# board.net
KiCad netlist of a schematic drawn in EAGLE
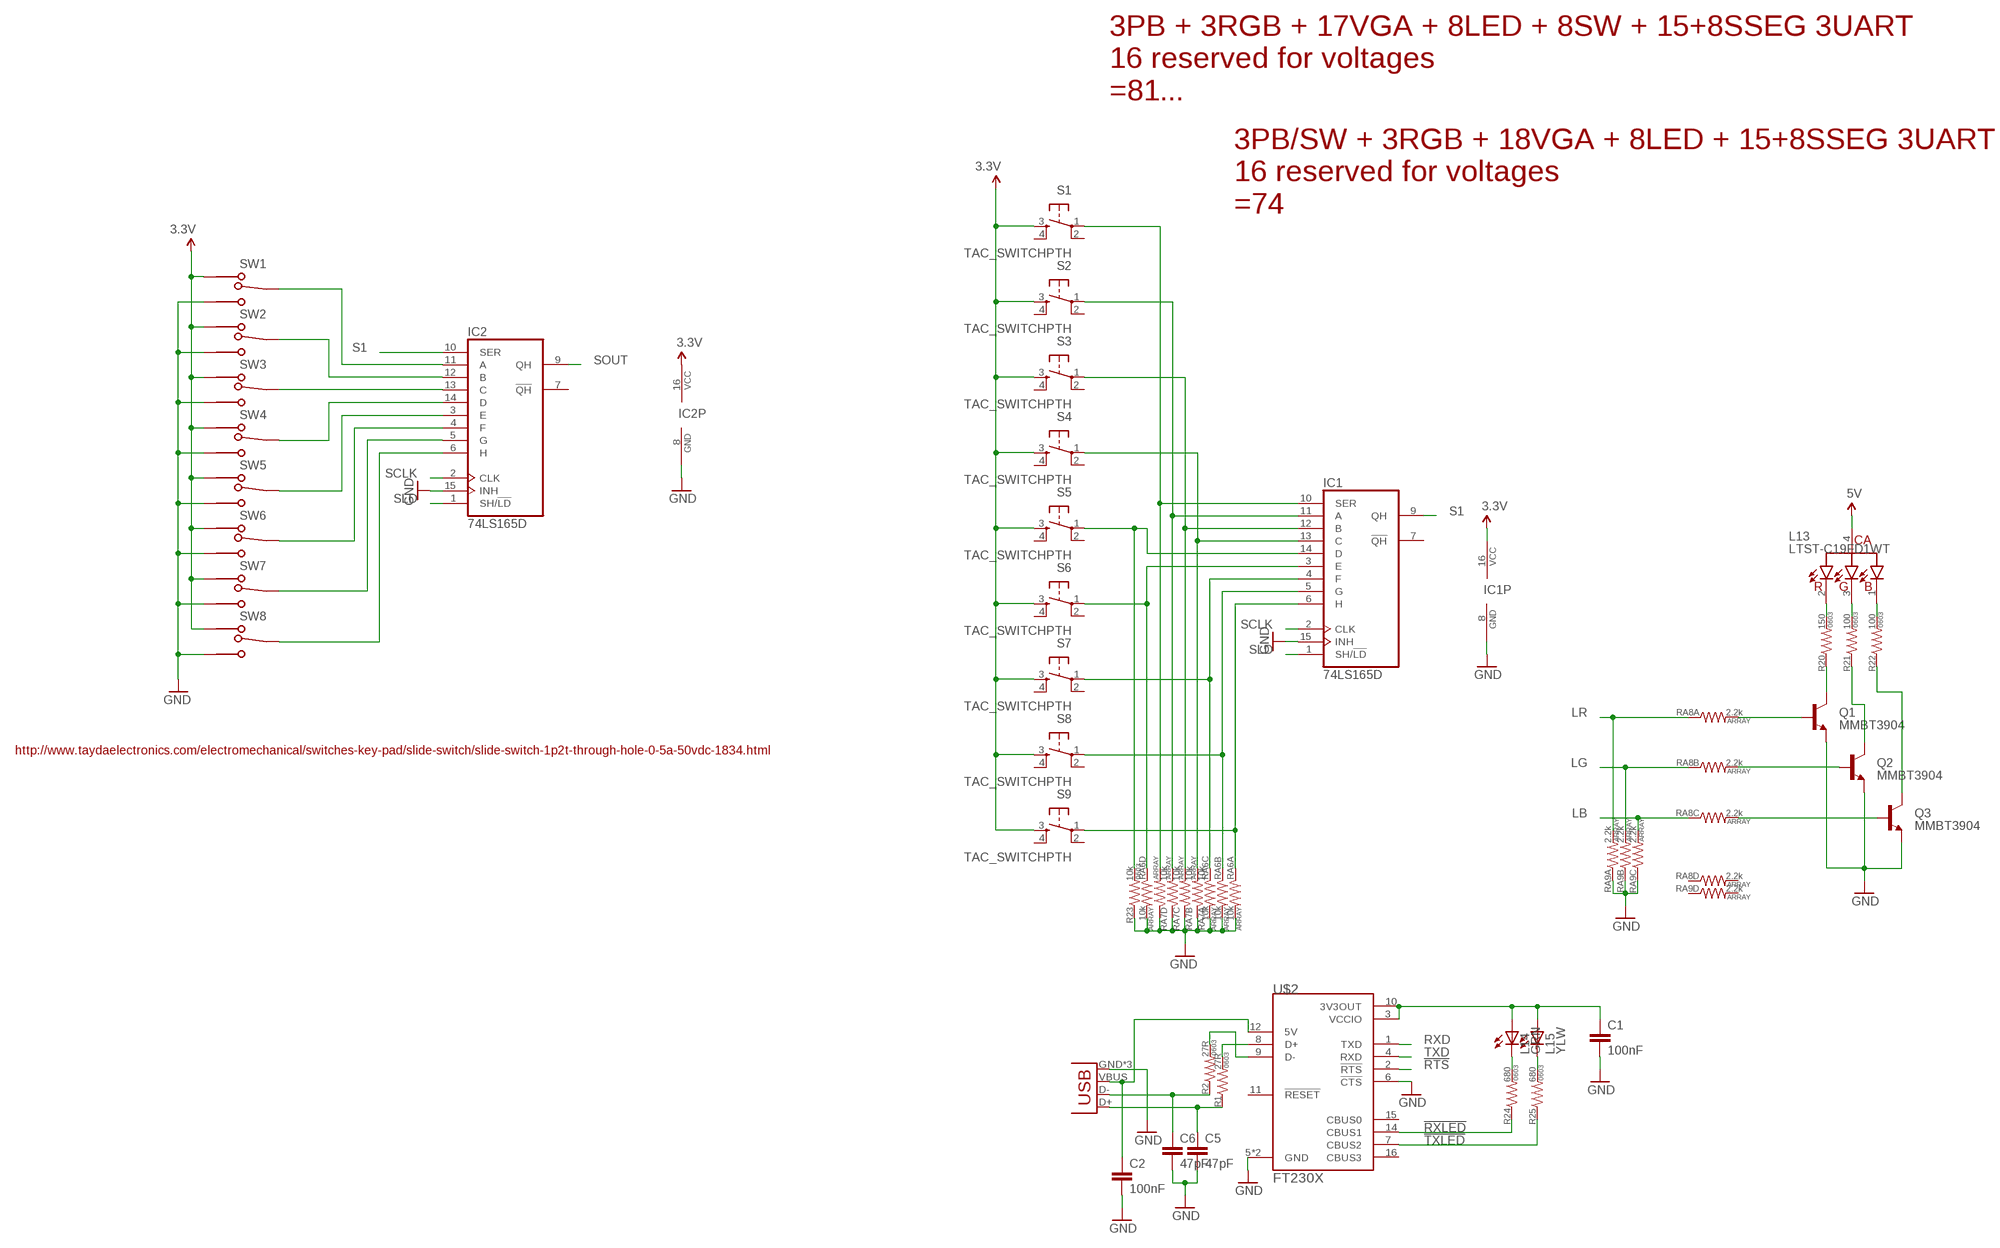
[diagram p0: schematic, sheet 1, part 1 of 3]
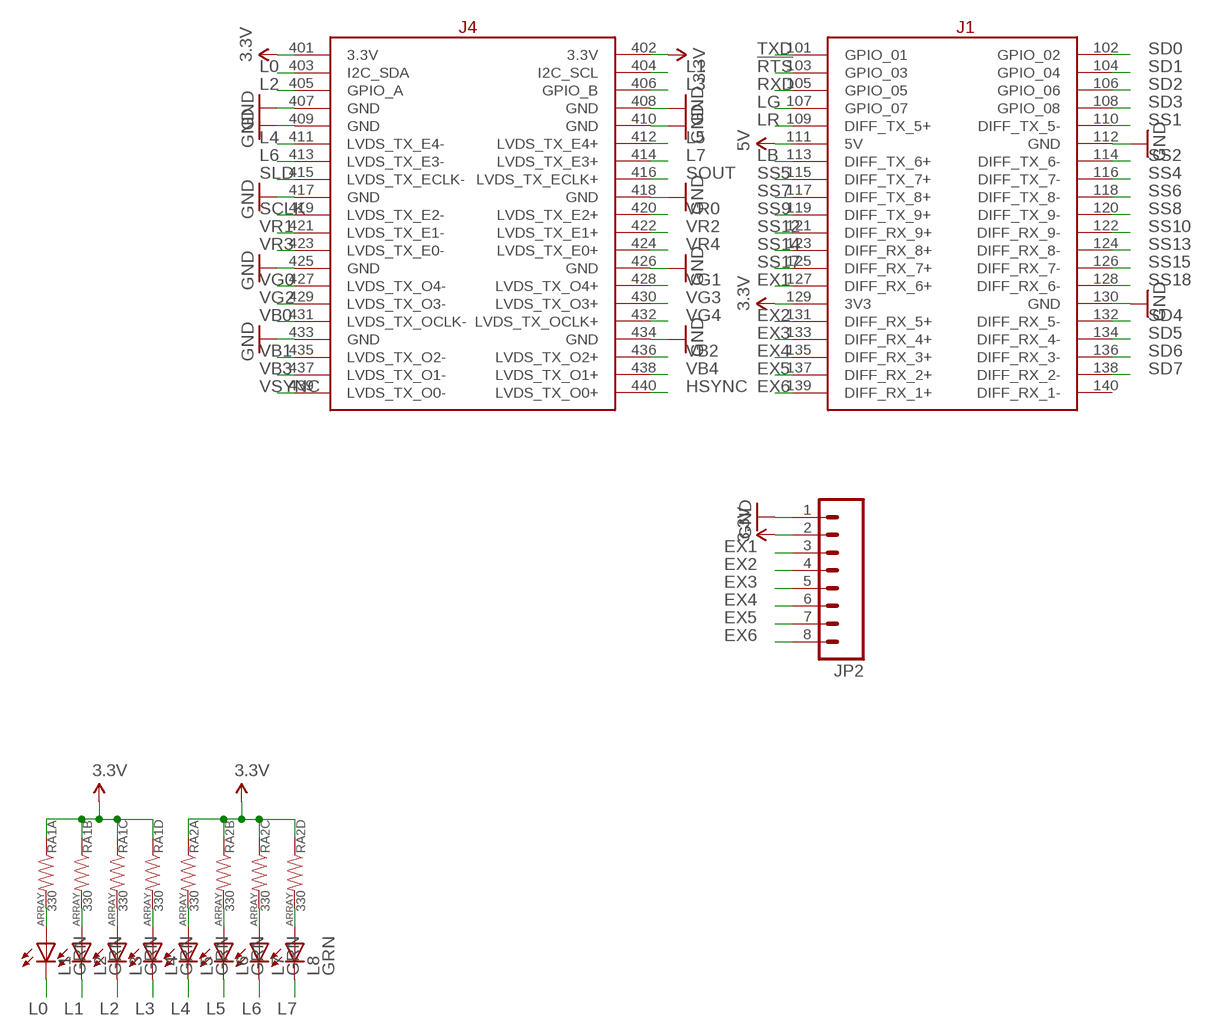
[diagram p1: schematic, sheet 1, part 2 of 3]
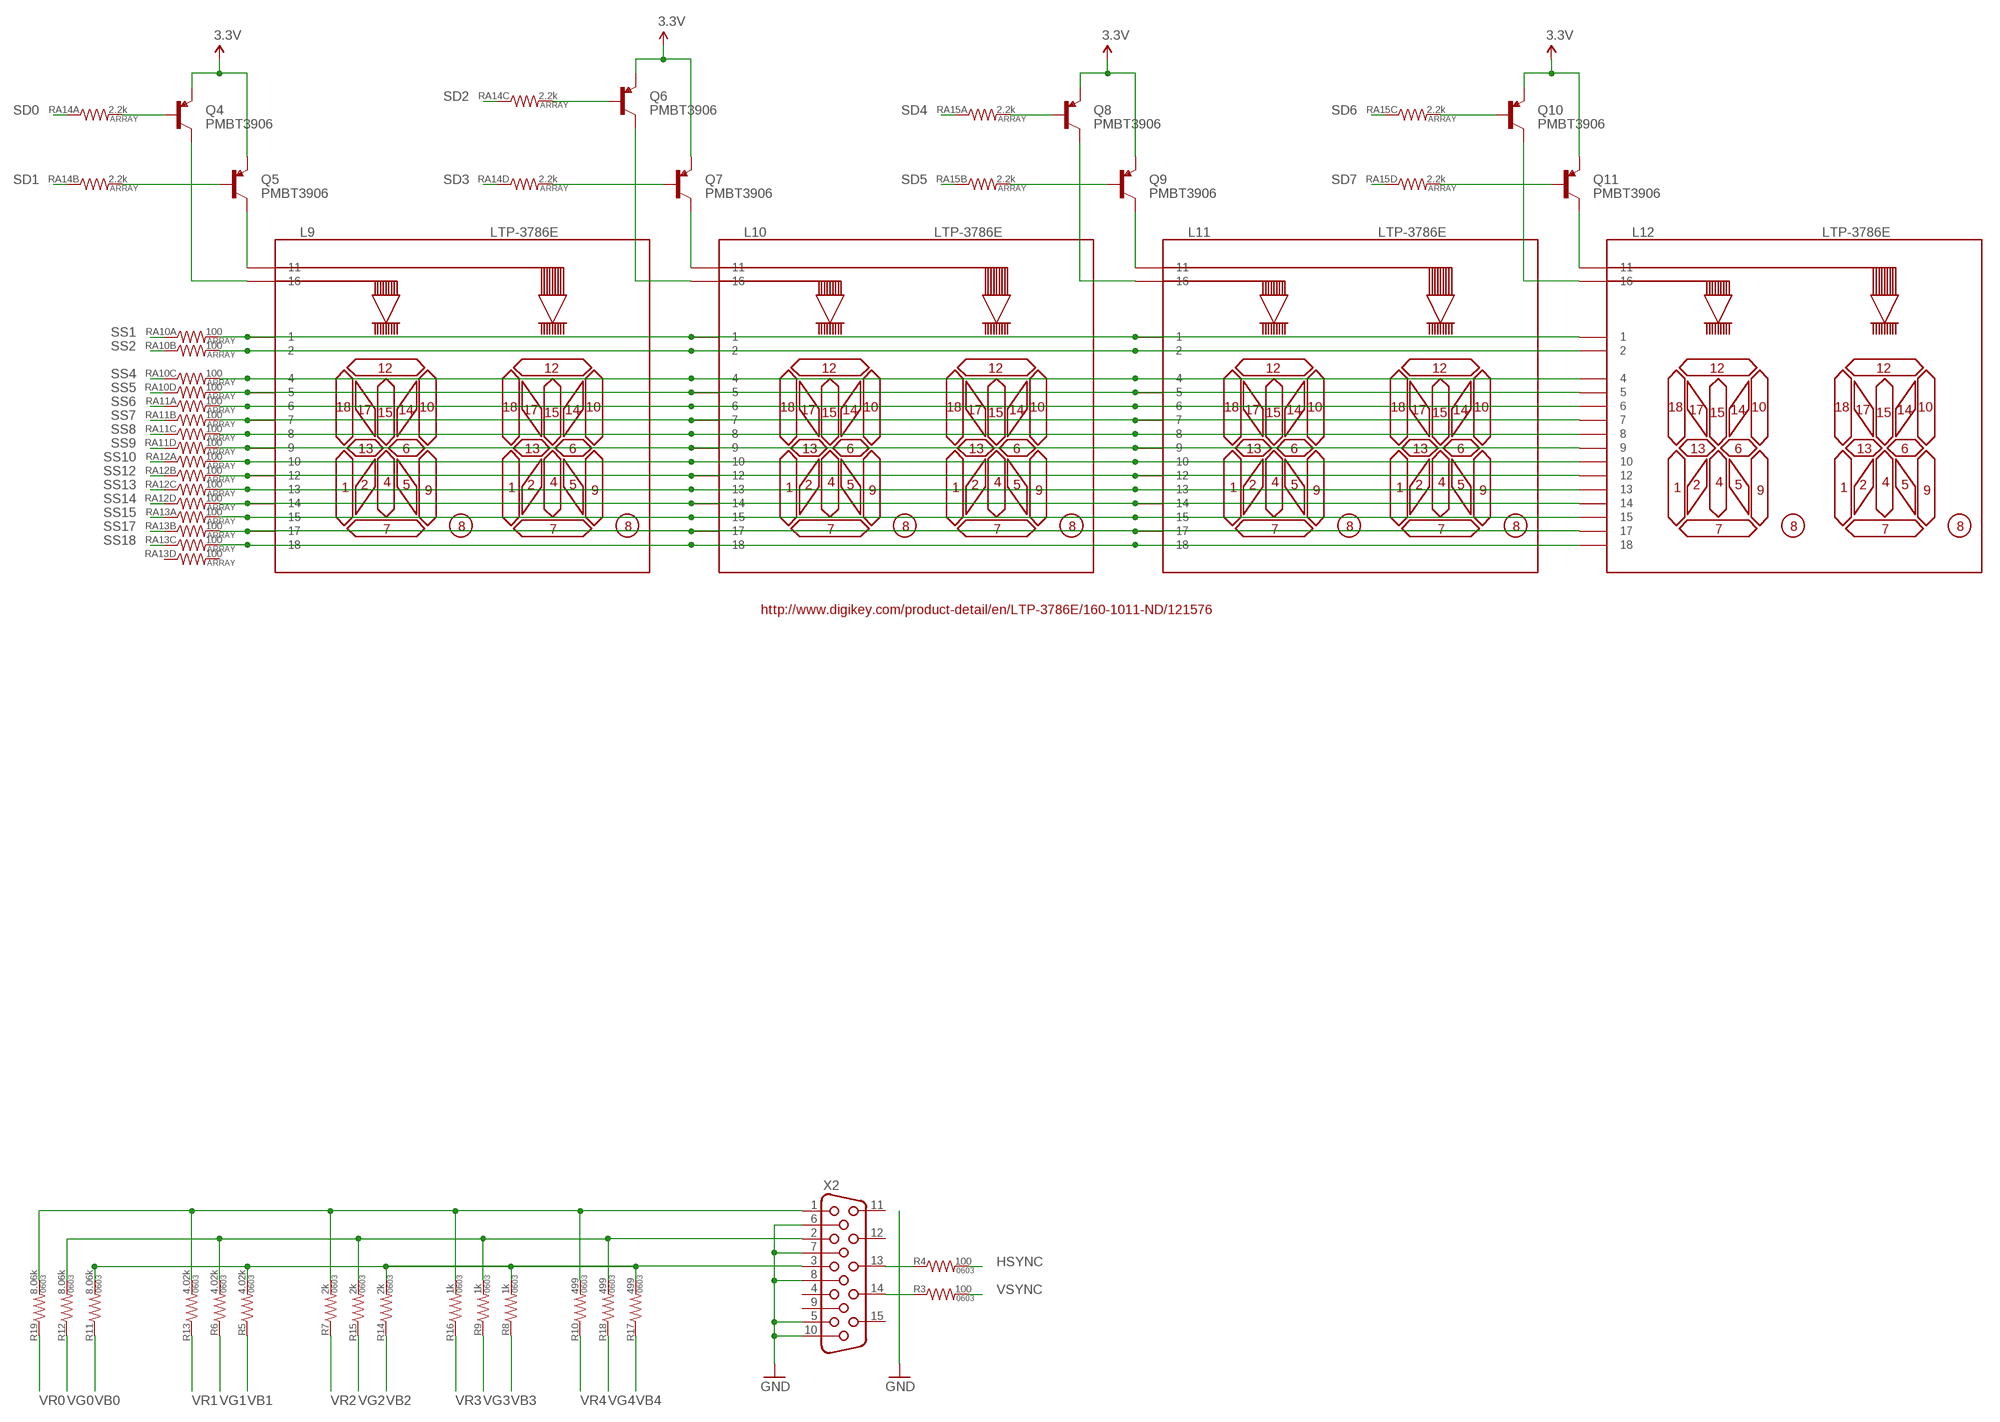
[diagram p2: schematic, sheet 1, part 3 of 3]

(export (version "E")
  (design (tool "Eeschema 10.0.6"))
  (components
    (comp (ref "C1")
      (value "100nF")
      (footprint "eagle-import:0402-CAP")
      (libsource (lib "eagle-import") (part "CAP0402-CAP"))
    )
    (comp (ref "C2")
      (value "100nF")
      (footprint "eagle-import:0402-CAP")
      (libsource (lib "eagle-import") (part "CAP0402-CAP"))
    )
    (comp (ref "C5")
      (value "47pF")
      (footprint "eagle-import:0402-CAP")
      (libsource (lib "eagle-import") (part "CAP0402-CAP"))
    )
    (comp (ref "C6")
      (value "47pF")
      (footprint "eagle-import:0402-CAP")
      (libsource (lib "eagle-import") (part "CAP0402-CAP"))
    )
    (comp (ref "IC1")
      (value "74LS165D")
      (footprint "eagle-import:SO16")
      (libsource (lib "eagle-import") (part "74165DLS"))
    )
    (comp (ref "IC2")
      (value "74LS165D")
      (footprint "eagle-import:SO16")
      (libsource (lib "eagle-import") (part "74165DLS"))
    )
    (comp (ref "JP1")
      (value "USB-MICROB")
      (footprint "eagle-import:USB-MICROB")
      (libsource (lib "eagle-import") (part "USB-MICROB"))
    )
    (comp (ref "JP2")
      (value "M081X08")
      (footprint "eagle-import:1X08")
      (libsource (lib "eagle-import") (part "M081X08"))
    )
    (comp (ref "L1")
      (value "GRN")
      (footprint "eagle-import:0603_LED")
      (libsource (lib "eagle-import") (part "LED0603"))
    )
    (comp (ref "L2")
      (value "GRN")
      (footprint "eagle-import:0603_LED")
      (libsource (lib "eagle-import") (part "LED0603"))
    )
    (comp (ref "L3")
      (value "GRN")
      (footprint "eagle-import:0603_LED")
      (libsource (lib "eagle-import") (part "LED0603"))
    )
    (comp (ref "L4")
      (value "GRN")
      (footprint "eagle-import:0603_LED")
      (libsource (lib "eagle-import") (part "LED0603"))
    )
    (comp (ref "L5")
      (value "GRN")
      (footprint "eagle-import:0603_LED")
      (libsource (lib "eagle-import") (part "LED0603"))
    )
    (comp (ref "L6")
      (value "GRN")
      (footprint "eagle-import:0603_LED")
      (libsource (lib "eagle-import") (part "LED0603"))
    )
    (comp (ref "L7")
      (value "GRN")
      (footprint "eagle-import:0603_LED")
      (libsource (lib "eagle-import") (part "LED0603"))
    )
    (comp (ref "L8")
      (value "GRN")
      (footprint "eagle-import:0603_LED")
      (libsource (lib "eagle-import") (part "LED0603"))
    )
    (comp (ref "L9")
      (value "LTP-3786E")
      (footprint "eagle-import:LTP-378_")
      (libsource (lib "eagle-import") (part "LTP-3786"))
    )
    (comp (ref "L10")
      (value "LTP-3786E")
      (footprint "eagle-import:LTP-378_")
      (libsource (lib "eagle-import") (part "LTP-3786"))
    )
    (comp (ref "L11")
      (value "LTP-3786E")
      (footprint "eagle-import:LTP-378_")
      (libsource (lib "eagle-import") (part "LTP-3786"))
    )
    (comp (ref "L12")
      (value "LTP-3786E")
      (footprint "eagle-import:LTP-378_")
      (libsource (lib "eagle-import") (part "LTP-3786"))
    )
    (comp (ref "L13")
      (value "LTST-C19FD1WT")
      (footprint "eagle-import:LTST-C19F")
      (libsource (lib "eagle-import") (part "LED_RGB"))
    )
    (comp (ref "L14")
      (value "GRN")
      (footprint "eagle-import:0603_LED")
      (libsource (lib "eagle-import") (part "LED0603"))
    )
    (comp (ref "L15")
      (value "YLW")
      (footprint "eagle-import:0603_LED")
      (libsource (lib "eagle-import") (part "LED0603"))
    )
    (comp (ref "Q1")
      (value "MMBT3904")
      (footprint "eagle-import:SOT23")
      (libsource (lib "eagle-import") (part "TRANSISTOR_NPNSOT23"))
    )
    (comp (ref "Q2")
      (value "MMBT3904")
      (footprint "eagle-import:SOT23")
      (libsource (lib "eagle-import") (part "TRANSISTOR_NPNSOT23"))
    )
    (comp (ref "Q3")
      (value "MMBT3904")
      (footprint "eagle-import:SOT23")
      (libsource (lib "eagle-import") (part "TRANSISTOR_NPNSOT23"))
    )
    (comp (ref "Q4")
      (value "PMBT3906")
      (footprint "eagle-import:SOT23-3")
      (libsource (lib "eagle-import") (part "TRANSISTOR_PNPPMBT3906"))
    )
    (comp (ref "Q5")
      (value "PMBT3906")
      (footprint "eagle-import:SOT23-3")
      (libsource (lib "eagle-import") (part "TRANSISTOR_PNPPMBT3906"))
    )
    (comp (ref "Q6")
      (value "PMBT3906")
      (footprint "eagle-import:SOT23-3")
      (libsource (lib "eagle-import") (part "TRANSISTOR_PNPPMBT3906"))
    )
    (comp (ref "Q7")
      (value "PMBT3906")
      (footprint "eagle-import:SOT23-3")
      (libsource (lib "eagle-import") (part "TRANSISTOR_PNPPMBT3906"))
    )
    (comp (ref "Q8")
      (value "PMBT3906")
      (footprint "eagle-import:SOT23-3")
      (libsource (lib "eagle-import") (part "TRANSISTOR_PNPPMBT3906"))
    )
    (comp (ref "Q9")
      (value "PMBT3906")
      (footprint "eagle-import:SOT23-3")
      (libsource (lib "eagle-import") (part "TRANSISTOR_PNPPMBT3906"))
    )
    (comp (ref "Q10")
      (value "PMBT3906")
      (footprint "eagle-import:SOT23-3")
      (libsource (lib "eagle-import") (part "TRANSISTOR_PNPPMBT3906"))
    )
    (comp (ref "Q11")
      (value "PMBT3906")
      (footprint "eagle-import:SOT23-3")
      (libsource (lib "eagle-import") (part "TRANSISTOR_PNPPMBT3906"))
    )
    (comp (ref "R1")
      (value "27R")
      (footprint "eagle-import:0603-RES")
      (libsource (lib "eagle-import") (part "RESISTOR0603"))
    )
    (comp (ref "R2")
      (value "27R")
      (footprint "eagle-import:0603-RES")
      (libsource (lib "eagle-import") (part "RESISTOR0603"))
    )
    (comp (ref "R3")
      (value "100")
      (footprint "eagle-import:0603-RES")
      (libsource (lib "eagle-import") (part "RESISTOR0603"))
    )
    (comp (ref "R4")
      (value "100")
      (footprint "eagle-import:0603-RES")
      (libsource (lib "eagle-import") (part "RESISTOR0603"))
    )
    (comp (ref "R5")
      (value "4.02k")
      (footprint "eagle-import:0603-RES")
      (libsource (lib "eagle-import") (part "RESISTOR0603"))
    )
    (comp (ref "R6")
      (value "4.02k")
      (footprint "eagle-import:0603-RES")
      (libsource (lib "eagle-import") (part "RESISTOR0603"))
    )
    (comp (ref "R7")
      (value "2k")
      (footprint "eagle-import:0603-RES")
      (libsource (lib "eagle-import") (part "RESISTOR0603"))
    )
    (comp (ref "R8")
      (value "1k")
      (footprint "eagle-import:0603-RES")
      (libsource (lib "eagle-import") (part "RESISTOR0603"))
    )
    (comp (ref "R9")
      (value "1k")
      (footprint "eagle-import:0603-RES")
      (libsource (lib "eagle-import") (part "RESISTOR0603"))
    )
    (comp (ref "R10")
      (value "499")
      (footprint "eagle-import:0603-RES")
      (libsource (lib "eagle-import") (part "RESISTOR0603"))
    )
    (comp (ref "R11")
      (value "8.06k")
      (footprint "eagle-import:0603-RES")
      (libsource (lib "eagle-import") (part "RESISTOR0603"))
    )
    (comp (ref "R12")
      (value "8.06k")
      (footprint "eagle-import:0603-RES")
      (libsource (lib "eagle-import") (part "RESISTOR0603"))
    )
    (comp (ref "R13")
      (value "4.02k")
      (footprint "eagle-import:0603-RES")
      (libsource (lib "eagle-import") (part "RESISTOR0603"))
    )
    (comp (ref "R14")
      (value "2k")
      (footprint "eagle-import:0603-RES")
      (libsource (lib "eagle-import") (part "RESISTOR0603"))
    )
    (comp (ref "R15")
      (value "2k")
      (footprint "eagle-import:0603-RES")
      (libsource (lib "eagle-import") (part "RESISTOR0603"))
    )
    (comp (ref "R16")
      (value "1k")
      (footprint "eagle-import:0603-RES")
      (libsource (lib "eagle-import") (part "RESISTOR0603"))
    )
    (comp (ref "R17")
      (value "499")
      (footprint "eagle-import:0603-RES")
      (libsource (lib "eagle-import") (part "RESISTOR0603"))
    )
    (comp (ref "R18")
      (value "499")
      (footprint "eagle-import:0603-RES")
      (libsource (lib "eagle-import") (part "RESISTOR0603"))
    )
    (comp (ref "R19")
      (value "8.06k")
      (footprint "eagle-import:0603-RES")
      (libsource (lib "eagle-import") (part "RESISTOR0603"))
    )
    (comp (ref "R20")
      (value "150")
      (footprint "eagle-import:0603-RES")
      (libsource (lib "eagle-import") (part "RESISTOR0603"))
    )
    (comp (ref "R21")
      (value "100")
      (footprint "eagle-import:0603-RES")
      (libsource (lib "eagle-import") (part "RESISTOR0603"))
    )
    (comp (ref "R22")
      (value "100")
      (footprint "eagle-import:0603-RES")
      (libsource (lib "eagle-import") (part "RESISTOR0603"))
    )
    (comp (ref "R23")
      (value "10k")
      (footprint "eagle-import:0603-RES")
      (libsource (lib "eagle-import") (part "RESISTOR0603"))
    )
    (comp (ref "R24")
      (value "680")
      (footprint "eagle-import:0603-RES")
      (libsource (lib "eagle-import") (part "RESISTOR0603"))
    )
    (comp (ref "R25")
      (value "680")
      (footprint "eagle-import:0603-RES")
      (libsource (lib "eagle-import") (part "RESISTOR0603"))
    )
    (comp (ref "RA1")
      (value "330")
      (footprint "eagle-import:0603-ARV")
      (libsource (lib "eagle-import") (part "RESISTOR_ARRAY0603_X4"))
    )
    (comp (ref "RA2")
      (value "330")
      (footprint "eagle-import:0603-ARV")
      (libsource (lib "eagle-import") (part "RESISTOR_ARRAY0603_X4"))
    )
    (comp (ref "RA6")
      (value "10k")
      (footprint "eagle-import:0603-ARV")
      (libsource (lib "eagle-import") (part "RESISTOR_ARRAY0603_X4"))
    )
    (comp (ref "RA7")
      (value "10k")
      (footprint "eagle-import:0603-ARV")
      (libsource (lib "eagle-import") (part "RESISTOR_ARRAY0603_X4"))
    )
    (comp (ref "RA8")
      (value "2.2k")
      (footprint "eagle-import:0603-ARV")
      (libsource (lib "eagle-import") (part "RESISTOR_ARRAY0603_X4"))
    )
    (comp (ref "RA9")
      (value "2.2k")
      (footprint "eagle-import:0603-ARV")
      (libsource (lib "eagle-import") (part "RESISTOR_ARRAY0603_X4"))
    )
    (comp (ref "RA10")
      (value "100")
      (footprint "eagle-import:0603-ARV")
      (libsource (lib "eagle-import") (part "RESISTOR_ARRAY0603_X4"))
    )
    (comp (ref "RA11")
      (value "100")
      (footprint "eagle-import:0603-ARV")
      (libsource (lib "eagle-import") (part "RESISTOR_ARRAY0603_X4"))
    )
    (comp (ref "RA12")
      (value "100")
      (footprint "eagle-import:0603-ARV")
      (libsource (lib "eagle-import") (part "RESISTOR_ARRAY0603_X4"))
    )
    (comp (ref "RA13")
      (value "100")
      (footprint "eagle-import:0603-ARV")
      (libsource (lib "eagle-import") (part "RESISTOR_ARRAY0603_X4"))
    )
    (comp (ref "RA14")
      (value "2.2k")
      (footprint "eagle-import:0603-ARV")
      (libsource (lib "eagle-import") (part "RESISTOR_ARRAY0603_X4"))
    )
    (comp (ref "RA15")
      (value "2.2k")
      (footprint "eagle-import:0603-ARV")
      (libsource (lib "eagle-import") (part "RESISTOR_ARRAY0603_X4"))
    )
    (comp (ref "S1")
      (value "TAC_SWITCHPTH")
      (footprint "eagle-import:TACTILE-PTH")
      (libsource (lib "eagle-import") (part "TAC_SWITCHPTH"))
    )
    (comp (ref "S2")
      (value "TAC_SWITCHPTH")
      (footprint "eagle-import:TACTILE-PTH")
      (libsource (lib "eagle-import") (part "TAC_SWITCHPTH"))
    )
    (comp (ref "S3")
      (value "TAC_SWITCHPTH")
      (footprint "eagle-import:TACTILE-PTH")
      (libsource (lib "eagle-import") (part "TAC_SWITCHPTH"))
    )
    (comp (ref "S4")
      (value "TAC_SWITCHPTH")
      (footprint "eagle-import:TACTILE-PTH")
      (libsource (lib "eagle-import") (part "TAC_SWITCHPTH"))
    )
    (comp (ref "S5")
      (value "TAC_SWITCHPTH")
      (footprint "eagle-import:TACTILE-PTH")
      (libsource (lib "eagle-import") (part "TAC_SWITCHPTH"))
    )
    (comp (ref "S6")
      (value "TAC_SWITCHPTH")
      (footprint "eagle-import:TACTILE-PTH")
      (libsource (lib "eagle-import") (part "TAC_SWITCHPTH"))
    )
    (comp (ref "S7")
      (value "TAC_SWITCHPTH")
      (footprint "eagle-import:TACTILE-PTH")
      (libsource (lib "eagle-import") (part "TAC_SWITCHPTH"))
    )
    (comp (ref "S8")
      (value "TAC_SWITCHPTH")
      (footprint "eagle-import:TACTILE-PTH")
      (libsource (lib "eagle-import") (part "TAC_SWITCHPTH"))
    )
    (comp (ref "S9")
      (value "TAC_SWITCHPTH")
      (footprint "eagle-import:TACTILE-PTH")
      (libsource (lib "eagle-import") (part "TAC_SWITCHPTH"))
    )
    (comp (ref "SW1")
      (value "SWITCH_SPDT")
      (footprint "eagle-import:SWITCH_SLIDE_SPDT")
      (libsource (lib "eagle-import") (part "SWITCH_SPDT"))
    )
    (comp (ref "SW2")
      (value "SWITCH_SPDT")
      (footprint "eagle-import:SWITCH_SLIDE_SPDT")
      (libsource (lib "eagle-import") (part "SWITCH_SPDT"))
    )
    (comp (ref "SW3")
      (value "SWITCH_SPDT")
      (footprint "eagle-import:SWITCH_SLIDE_SPDT")
      (libsource (lib "eagle-import") (part "SWITCH_SPDT"))
    )
    (comp (ref "SW4")
      (value "SWITCH_SPDT")
      (footprint "eagle-import:SWITCH_SLIDE_SPDT")
      (libsource (lib "eagle-import") (part "SWITCH_SPDT"))
    )
    (comp (ref "SW5")
      (value "SWITCH_SPDT")
      (footprint "eagle-import:SWITCH_SLIDE_SPDT")
      (libsource (lib "eagle-import") (part "SWITCH_SPDT"))
    )
    (comp (ref "SW6")
      (value "SWITCH_SPDT")
      (footprint "eagle-import:SWITCH_SLIDE_SPDT")
      (libsource (lib "eagle-import") (part "SWITCH_SPDT"))
    )
    (comp (ref "SW7")
      (value "SWITCH_SPDT")
      (footprint "eagle-import:SWITCH_SLIDE_SPDT")
      (libsource (lib "eagle-import") (part "SWITCH_SPDT"))
    )
    (comp (ref "SW8")
      (value "SWITCH_SPDT")
      (footprint "eagle-import:SWITCH_SLIDE_SPDT")
      (libsource (lib "eagle-import") (part "SWITCH_SPDT"))
    )
    (comp (ref "U$2")
      (value "FT230X")
      (footprint "eagle-import:TSSOP16")
      (libsource (lib "eagle-import") (part "FT230X"))
    )
    (comp (ref "U$3")
      (value "BEMICROCV_SHIELD")
      (footprint "eagle-import:BEMICROCV_SHIELD")
      (libsource (lib "eagle-import") (part "BEMICROCV_SHIELD"))
    )
    (comp (ref "X2")
      (value "HF15H")
      (footprint "eagle-import:HDF15H")
      (libsource (lib "eagle-import") (part "HF15H"))
    )
  )
  (nets
    (net (code "1") (name "/EX1") (class "Default")
      (node (ref "JP2") (pin "3") (pinfunction "3_3") (pintype "passive"))
      (node (ref "U$3") (pin "127") (pinfunction "DIFF_RX_6+_127") (pintype "bidirectional"))
    )
    (net (code "2") (name "/EX2") (class "Default")
      (node (ref "JP2") (pin "4") (pinfunction "4_4") (pintype "passive"))
      (node (ref "U$3") (pin "131") (pinfunction "DIFF_RX_5+_131") (pintype "bidirectional"))
    )
    (net (code "3") (name "/EX3") (class "Default")
      (node (ref "JP2") (pin "5") (pinfunction "5_5") (pintype "passive"))
      (node (ref "U$3") (pin "133") (pinfunction "DIFF_RX_4+_133") (pintype "bidirectional"))
    )
    (net (code "4") (name "/EX4") (class "Default")
      (node (ref "JP2") (pin "6") (pinfunction "6_6") (pintype "passive"))
      (node (ref "U$3") (pin "135") (pinfunction "DIFF_RX_3+_135") (pintype "bidirectional"))
    )
    (net (code "5") (name "/EX5") (class "Default")
      (node (ref "JP2") (pin "7") (pinfunction "7_7") (pintype "passive"))
      (node (ref "U$3") (pin "137") (pinfunction "DIFF_RX_2+_137") (pintype "bidirectional"))
    )
    (net (code "6") (name "/EX6") (class "Default")
      (node (ref "JP2") (pin "8") (pinfunction "8_8") (pintype "passive"))
      (node (ref "U$3") (pin "139") (pinfunction "DIFF_RX_1+_139") (pintype "bidirectional"))
    )
    (net (code "7") (name "/HSYNC") (class "Default")
      (node (ref "R4") (pin "2") (pinfunction "2_2") (pintype "passive"))
      (node (ref "U$3") (pin "440") (pinfunction "LVDS_TX_O0+_440") (pintype "bidirectional"))
    )
    (net (code "8") (name "/L0") (class "Default")
      (node (ref "L1") (pin "C") (pinfunction "C_C") (pintype "passive"))
      (node (ref "U$3") (pin "403") (pinfunction "I2C_SDA_403") (pintype "bidirectional"))
    )
    (net (code "9") (name "/L1") (class "Default")
      (node (ref "L2") (pin "C") (pinfunction "C_C") (pintype "passive"))
      (node (ref "U$3") (pin "404") (pinfunction "I2C_SCL_404") (pintype "bidirectional"))
    )
    (net (code "10") (name "/L2") (class "Default")
      (node (ref "L3") (pin "C") (pinfunction "C_C") (pintype "passive"))
      (node (ref "U$3") (pin "405") (pinfunction "GPIO_A_405") (pintype "bidirectional"))
    )
    (net (code "11") (name "/L3") (class "Default")
      (node (ref "L4") (pin "C") (pinfunction "C_C") (pintype "passive"))
      (node (ref "U$3") (pin "406") (pinfunction "GPIO_B_406") (pintype "bidirectional"))
    )
    (net (code "12") (name "/L4") (class "Default")
      (node (ref "L5") (pin "C") (pinfunction "C_C") (pintype "passive"))
      (node (ref "U$3") (pin "411") (pinfunction "LVDS_TX_E4-_411") (pintype "bidirectional"))
    )
    (net (code "13") (name "/L5") (class "Default")
      (node (ref "L6") (pin "C") (pinfunction "C_C") (pintype "passive"))
      (node (ref "U$3") (pin "412") (pinfunction "LVDS_TX_E4+_412") (pintype "bidirectional"))
    )
    (net (code "14") (name "/L6") (class "Default")
      (node (ref "L7") (pin "C") (pinfunction "C_C") (pintype "passive"))
      (node (ref "U$3") (pin "413") (pinfunction "LVDS_TX_E3-_413") (pintype "bidirectional"))
    )
    (net (code "15") (name "/L7") (class "Default")
      (node (ref "L8") (pin "C") (pinfunction "C_C") (pintype "passive"))
      (node (ref "U$3") (pin "414") (pinfunction "LVDS_TX_E3+_414") (pintype "bidirectional"))
    )
    (net (code "16") (name "/LB") (class "Default")
      (node (ref "RA8") (pin "3") (pinfunction "1_3") (pintype "passive"))
      (node (ref "RA9") (pin "6") (pinfunction "2_6") (pintype "passive"))
      (node (ref "U$3") (pin "113") (pinfunction "DIFF_TX_6+_113") (pintype "bidirectional"))
    )
    (net (code "17") (name "/LG") (class "Default")
      (node (ref "RA8") (pin "2") (pinfunction "1_2") (pintype "passive"))
      (node (ref "RA9") (pin "7") (pinfunction "2_7") (pintype "passive"))
      (node (ref "U$3") (pin "107") (pinfunction "GPIO_07_107") (pintype "bidirectional"))
    )
    (net (code "18") (name "/LR") (class "Default")
      (node (ref "RA8") (pin "1") (pinfunction "1_1") (pintype "passive"))
      (node (ref "RA9") (pin "8") (pinfunction "2_8") (pintype "passive"))
      (node (ref "U$3") (pin "109") (pinfunction "DIFF_TX_5+_109") (pintype "bidirectional"))
    )
    (net (code "19") (name "/RXD") (class "Default")
      (node (ref "U$2") (pin "1") (pinfunction "TXD_1") (pintype "bidirectional"))
      (node (ref "U$3") (pin "105") (pinfunction "GPIO_05_105") (pintype "bidirectional"))
    )
    (net (code "20") (name "/S1") (class "Default")
      (node (ref "IC1") (pin "9") (pinfunction "QH_9") (pintype "output"))
      (node (ref "IC2") (pin "10") (pinfunction "SER_10") (pintype "input"))
    )
    (net (code "21") (name "/SCLK") (class "Default")
      (node (ref "IC1") (pin "2") (pinfunction "CLK_2") (pintype "input"))
      (node (ref "IC2") (pin "2") (pinfunction "CLK_2") (pintype "input"))
      (node (ref "U$3") (pin "419") (pinfunction "LVDS_TX_E2-_419") (pintype "bidirectional"))
    )
    (net (code "22") (name "/SD0") (class "Default")
      (node (ref "RA14") (pin "1") (pinfunction "1_1") (pintype "passive"))
      (node (ref "U$3") (pin "102") (pinfunction "GPIO_02_102") (pintype "bidirectional"))
    )
    (net (code "23") (name "/SD1") (class "Default")
      (node (ref "RA14") (pin "2") (pinfunction "1_2") (pintype "passive"))
      (node (ref "U$3") (pin "104") (pinfunction "GPIO_04_104") (pintype "bidirectional"))
    )
    (net (code "24") (name "/SD2") (class "Default")
      (node (ref "RA14") (pin "3") (pinfunction "1_3") (pintype "passive"))
      (node (ref "U$3") (pin "106") (pinfunction "GPIO_06_106") (pintype "bidirectional"))
    )
    (net (code "25") (name "/SD3") (class "Default")
      (node (ref "RA14") (pin "4") (pinfunction "1_4") (pintype "passive"))
      (node (ref "U$3") (pin "108") (pinfunction "GPIO_08_108") (pintype "bidirectional"))
    )
    (net (code "26") (name "/SD4") (class "Default")
      (node (ref "RA15") (pin "1") (pinfunction "1_1") (pintype "passive"))
      (node (ref "U$3") (pin "132") (pinfunction "DIFF_RX_5-_132") (pintype "bidirectional"))
    )
    (net (code "27") (name "/SD5") (class "Default")
      (node (ref "RA15") (pin "2") (pinfunction "1_2") (pintype "passive"))
      (node (ref "U$3") (pin "134") (pinfunction "DIFF_RX_4-_134") (pintype "bidirectional"))
    )
    (net (code "28") (name "/SD6") (class "Default")
      (node (ref "RA15") (pin "3") (pinfunction "1_3") (pintype "passive"))
      (node (ref "U$3") (pin "136") (pinfunction "DIFF_RX_3-_136") (pintype "bidirectional"))
    )
    (net (code "29") (name "/SD7") (class "Default")
      (node (ref "RA15") (pin "4") (pinfunction "1_4") (pintype "passive"))
      (node (ref "U$3") (pin "138") (pinfunction "DIFF_RX_2-_138") (pintype "bidirectional"))
    )
    (net (code "30") (name "/SLD") (class "Default")
      (node (ref "IC1") (pin "1") (pinfunction "SH/~{LD}_1") (pintype "input"))
      (node (ref "IC2") (pin "1") (pinfunction "SH/~{LD}_1") (pintype "input"))
      (node (ref "U$3") (pin "415") (pinfunction "LVDS_TX_ECLK-_415") (pintype "bidirectional"))
    )
    (net (code "31") (name "/SOUT") (class "Default")
      (node (ref "IC2") (pin "9") (pinfunction "QH_9") (pintype "output"))
      (node (ref "U$3") (pin "416") (pinfunction "LVDS_TX_ECLK+_416") (pintype "bidirectional"))
    )
    (net (code "32") (name "/SS1") (class "Default")
      (node (ref "RA10") (pin "1") (pinfunction "1_1") (pintype "passive"))
      (node (ref "U$3") (pin "110") (pinfunction "DIFF_TX_5-_110") (pintype "bidirectional"))
    )
    (net (code "33") (name "/SS2") (class "Default")
      (node (ref "RA10") (pin "2") (pinfunction "1_2") (pintype "passive"))
      (node (ref "U$3") (pin "114") (pinfunction "DIFF_TX_6-_114") (pintype "bidirectional"))
    )
    (net (code "34") (name "/SS4") (class "Default")
      (node (ref "RA10") (pin "3") (pinfunction "1_3") (pintype "passive"))
      (node (ref "U$3") (pin "116") (pinfunction "DIFF_TX_7-_116") (pintype "bidirectional"))
    )
    (net (code "35") (name "/SS5") (class "Default")
      (node (ref "RA10") (pin "4") (pinfunction "1_4") (pintype "passive"))
      (node (ref "U$3") (pin "115") (pinfunction "DIFF_TX_7+_115") (pintype "bidirectional"))
    )
    (net (code "36") (name "/SS6") (class "Default")
      (node (ref "RA11") (pin "1") (pinfunction "1_1") (pintype "passive"))
      (node (ref "U$3") (pin "118") (pinfunction "DIFF_TX_8-_118") (pintype "bidirectional"))
    )
    (net (code "37") (name "/SS7") (class "Default")
      (node (ref "RA11") (pin "2") (pinfunction "1_2") (pintype "passive"))
      (node (ref "U$3") (pin "117") (pinfunction "DIFF_TX_8+_117") (pintype "bidirectional"))
    )
    (net (code "38") (name "/SS8") (class "Default")
      (node (ref "RA11") (pin "3") (pinfunction "1_3") (pintype "passive"))
      (node (ref "U$3") (pin "120") (pinfunction "DIFF_TX_9-_120") (pintype "bidirectional"))
    )
    (net (code "39") (name "/SS9") (class "Default")
      (node (ref "RA11") (pin "4") (pinfunction "1_4") (pintype "passive"))
      (node (ref "U$3") (pin "119") (pinfunction "DIFF_TX_9+_119") (pintype "bidirectional"))
    )
    (net (code "40") (name "/SS10") (class "Default")
      (node (ref "RA12") (pin "1") (pinfunction "1_1") (pintype "passive"))
      (node (ref "U$3") (pin "122") (pinfunction "DIFF_RX_9-_122") (pintype "bidirectional"))
    )
    (net (code "41") (name "/SS12") (class "Default")
      (node (ref "RA12") (pin "2") (pinfunction "1_2") (pintype "passive"))
      (node (ref "U$3") (pin "121") (pinfunction "DIFF_RX_9+_121") (pintype "bidirectional"))
    )
    (net (code "42") (name "/SS13") (class "Default")
      (node (ref "RA12") (pin "3") (pinfunction "1_3") (pintype "passive"))
      (node (ref "U$3") (pin "124") (pinfunction "DIFF_RX_8-_124") (pintype "bidirectional"))
    )
    (net (code "43") (name "/SS14") (class "Default")
      (node (ref "RA12") (pin "4") (pinfunction "1_4") (pintype "passive"))
      (node (ref "U$3") (pin "123") (pinfunction "DIFF_RX_8+_123") (pintype "bidirectional"))
    )
    (net (code "44") (name "/SS15") (class "Default")
      (node (ref "RA13") (pin "1") (pinfunction "1_1") (pintype "passive"))
      (node (ref "U$3") (pin "126") (pinfunction "DIFF_RX_7-_126") (pintype "bidirectional"))
    )
    (net (code "45") (name "/SS17") (class "Default")
      (node (ref "RA13") (pin "2") (pinfunction "1_2") (pintype "passive"))
      (node (ref "U$3") (pin "125") (pinfunction "DIFF_RX_7+_125") (pintype "bidirectional"))
    )
    (net (code "46") (name "/SS18") (class "Default")
      (node (ref "RA13") (pin "3") (pinfunction "1_3") (pintype "passive"))
      (node (ref "U$3") (pin "128") (pinfunction "DIFF_RX_6-_128") (pintype "bidirectional"))
    )
    (net (code "47") (name "/TXD") (class "Default")
      (node (ref "U$2") (pin "4") (pinfunction "RXD_4") (pintype "bidirectional"))
      (node (ref "U$3") (pin "101") (pinfunction "GPIO_01_101") (pintype "bidirectional"))
    )
    (net (code "48") (name "/VB0") (class "Default")
      (node (ref "R11") (pin "1") (pinfunction "1_1") (pintype "passive"))
      (node (ref "U$3") (pin "431") (pinfunction "LVDS_TX_OCLK-_431") (pintype "bidirectional"))
    )
    (net (code "49") (name "/VB1") (class "Default")
      (node (ref "R5") (pin "1") (pinfunction "1_1") (pintype "passive"))
      (node (ref "U$3") (pin "435") (pinfunction "LVDS_TX_O2-_435") (pintype "bidirectional"))
    )
    (net (code "50") (name "/VB2") (class "Default")
      (node (ref "R14") (pin "1") (pinfunction "1_1") (pintype "passive"))
      (node (ref "U$3") (pin "436") (pinfunction "LVDS_TX_O2+_436") (pintype "bidirectional"))
    )
    (net (code "51") (name "/VB3") (class "Default")
      (node (ref "R8") (pin "1") (pinfunction "1_1") (pintype "passive"))
      (node (ref "U$3") (pin "437") (pinfunction "LVDS_TX_O1-_437") (pintype "bidirectional"))
    )
    (net (code "52") (name "/VB4") (class "Default")
      (node (ref "R17") (pin "1") (pinfunction "1_1") (pintype "passive"))
      (node (ref "U$3") (pin "438") (pinfunction "LVDS_TX_O1+_438") (pintype "bidirectional"))
    )
    (net (code "53") (name "/VG0") (class "Default")
      (node (ref "R12") (pin "1") (pinfunction "1_1") (pintype "passive"))
      (node (ref "U$3") (pin "427") (pinfunction "LVDS_TX_O4-_427") (pintype "bidirectional"))
    )
    (net (code "54") (name "/VG1") (class "Default")
      (node (ref "R6") (pin "1") (pinfunction "1_1") (pintype "passive"))
      (node (ref "U$3") (pin "428") (pinfunction "LVDS_TX_O4+_428") (pintype "bidirectional"))
    )
    (net (code "55") (name "/VG2") (class "Default")
      (node (ref "R15") (pin "1") (pinfunction "1_1") (pintype "passive"))
      (node (ref "U$3") (pin "429") (pinfunction "LVDS_TX_O3-_429") (pintype "bidirectional"))
    )
    (net (code "56") (name "/VG3") (class "Default")
      (node (ref "R9") (pin "1") (pinfunction "1_1") (pintype "passive"))
      (node (ref "U$3") (pin "430") (pinfunction "LVDS_TX_O3+_430") (pintype "bidirectional"))
    )
    (net (code "57") (name "/VG4") (class "Default")
      (node (ref "R18") (pin "1") (pinfunction "1_1") (pintype "passive"))
      (node (ref "U$3") (pin "432") (pinfunction "LVDS_TX_OCLK+_432") (pintype "bidirectional"))
    )
    (net (code "58") (name "/VR0") (class "Default")
      (node (ref "R19") (pin "1") (pinfunction "1_1") (pintype "passive"))
      (node (ref "U$3") (pin "420") (pinfunction "LVDS_TX_E2+_420") (pintype "bidirectional"))
    )
    (net (code "59") (name "/VR1") (class "Default")
      (node (ref "R13") (pin "1") (pinfunction "1_1") (pintype "passive"))
      (node (ref "U$3") (pin "421") (pinfunction "LVDS_TX_E1-_421") (pintype "bidirectional"))
    )
    (net (code "60") (name "/VR2") (class "Default")
      (node (ref "R7") (pin "1") (pinfunction "1_1") (pintype "passive"))
      (node (ref "U$3") (pin "422") (pinfunction "LVDS_TX_E1+_422") (pintype "bidirectional"))
    )
    (net (code "61") (name "/VR3") (class "Default")
      (node (ref "R16") (pin "1") (pinfunction "1_1") (pintype "passive"))
      (node (ref "U$3") (pin "423") (pinfunction "LVDS_TX_E0-_423") (pintype "bidirectional"))
    )
    (net (code "62") (name "/VR4") (class "Default")
      (node (ref "R10") (pin "1") (pinfunction "1_1") (pintype "passive"))
      (node (ref "U$3") (pin "424") (pinfunction "LVDS_TX_E0+_424") (pintype "bidirectional"))
    )
    (net (code "63") (name "/VSYNC") (class "Default")
      (node (ref "R3") (pin "2") (pinfunction "2_2") (pintype "passive"))
      (node (ref "U$3") (pin "439") (pinfunction "LVDS_TX_O0-_439") (pintype "bidirectional"))
    )
    (net (code "64") (name "/~{RTS}") (class "Default")
      (node (ref "U$2") (pin "2") (pinfunction "~{RTS}_2") (pintype "bidirectional"))
      (node (ref "U$3") (pin "103") (pinfunction "GPIO_03_103") (pintype "bidirectional"))
    )
    (net (code "65") (name "/~{RXLED}") (class "Default")
      (node (ref "R24") (pin "1") (pinfunction "1_1") (pintype "passive"))
      (node (ref "U$2") (pin "14") (pinfunction "CBUS1_14") (pintype "bidirectional"))
    )
    (net (code "66") (name "/~{TXLED}") (class "Default")
      (node (ref "R25") (pin "1") (pinfunction "1_1") (pintype "passive"))
      (node (ref "U$2") (pin "7") (pinfunction "CBUS2_7") (pintype "bidirectional"))
    )
    (net (code "67") (name "3.3V") (class "Default")
      (node (ref "IC1") (pin "16") (pinfunction "VCC_16") (pintype "power_in"))
      (node (ref "IC2") (pin "16") (pinfunction "VCC_16") (pintype "power_in"))
      (node (ref "JP2") (pin "2") (pinfunction "2_2") (pintype "passive"))
      (node (ref "Q10") (pin "2") (pinfunction "E_2") (pintype "passive"))
      (node (ref "Q11") (pin "2") (pinfunction "E_2") (pintype "passive"))
      (node (ref "Q4") (pin "2") (pinfunction "E_2") (pintype "passive"))
      (node (ref "Q5") (pin "2") (pinfunction "E_2") (pintype "passive"))
      (node (ref "Q6") (pin "2") (pinfunction "E_2") (pintype "passive"))
      (node (ref "Q7") (pin "2") (pinfunction "E_2") (pintype "passive"))
      (node (ref "Q8") (pin "2") (pinfunction "E_2") (pintype "passive"))
      (node (ref "Q9") (pin "2") (pinfunction "E_2") (pintype "passive"))
      (node (ref "RA1") (pin "1") (pinfunction "1_1") (pintype "passive"))
      (node (ref "RA1") (pin "2") (pinfunction "1_2") (pintype "passive"))
      (node (ref "RA1") (pin "3") (pinfunction "1_3") (pintype "passive"))
      (node (ref "RA1") (pin "4") (pinfunction "1_4") (pintype "passive"))
      (node (ref "RA2") (pin "1") (pinfunction "1_1") (pintype "passive"))
      (node (ref "RA2") (pin "2") (pinfunction "1_2") (pintype "passive"))
      (node (ref "RA2") (pin "3") (pinfunction "1_3") (pintype "passive"))
      (node (ref "RA2") (pin "4") (pinfunction "1_4") (pintype "passive"))
      (node (ref "S1") (pin "3") (pinfunction "3_3") (pintype "passive"))
      (node (ref "S2") (pin "3") (pinfunction "3_3") (pintype "passive"))
      (node (ref "S3") (pin "3") (pinfunction "3_3") (pintype "passive"))
      (node (ref "S4") (pin "3") (pinfunction "3_3") (pintype "passive"))
      (node (ref "S5") (pin "3") (pinfunction "3_3") (pintype "passive"))
      (node (ref "S6") (pin "3") (pinfunction "3_3") (pintype "passive"))
      (node (ref "S7") (pin "3") (pinfunction "3_3") (pintype "passive"))
      (node (ref "S8") (pin "3") (pinfunction "3_3") (pintype "passive"))
      (node (ref "S9") (pin "3") (pinfunction "3_3") (pintype "passive"))
      (node (ref "SW1") (pin "P1") (pinfunction "P1_P1") (pintype "bidirectional"))
      (node (ref "SW2") (pin "P1") (pinfunction "P1_P1") (pintype "bidirectional"))
      (node (ref "SW3") (pin "P1") (pinfunction "P1_P1") (pintype "bidirectional"))
      (node (ref "SW4") (pin "P1") (pinfunction "P1_P1") (pintype "bidirectional"))
      (node (ref "SW5") (pin "P1") (pinfunction "P1_P1") (pintype "bidirectional"))
      (node (ref "SW6") (pin "P1") (pinfunction "P1_P1") (pintype "bidirectional"))
      (node (ref "SW7") (pin "P1") (pinfunction "P1_P1") (pintype "bidirectional"))
      (node (ref "SW8") (pin "P1") (pinfunction "P1_P1") (pintype "bidirectional"))
      (node (ref "U$3") (pin "129") (pinfunction "3V3_129") (pintype "bidirectional"))
      (node (ref "U$3") (pin "401") (pinfunction "3.3V_401") (pintype "bidirectional"))
      (node (ref "U$3") (pin "402") (pinfunction "3.3V_402") (pintype "bidirectional"))
    )
    (net (code "68") (name "5V") (class "Default")
      (node (ref "L13") (pin "4") (pinfunction "CA_4") (pintype "passive"))
      (node (ref "U$3") (pin "111") (pinfunction "5V_111") (pintype "bidirectional"))
    )
    (net (code "69") (name "GND") (class "Default")
      (node (ref "C1") (pin "2") (pinfunction "2_2") (pintype "passive"))
      (node (ref "C2") (pin "2") (pinfunction "2_2") (pintype "passive"))
      (node (ref "C5") (pin "2") (pinfunction "2_2") (pintype "passive"))
      (node (ref "C6") (pin "2") (pinfunction "2_2") (pintype "passive"))
      (node (ref "IC1") (pin "15") (pinfunction "INH_15") (pintype "input"))
      (node (ref "IC1") (pin "8") (pinfunction "GND_8") (pintype "power_in"))
      (node (ref "IC2") (pin "15") (pinfunction "INH_15") (pintype "input"))
      (node (ref "IC2") (pin "8") (pinfunction "GND_8") (pintype "power_in"))
      (node (ref "JP1") (pin "GND") (pinfunction "GND_GND") (pintype "bidirectional"))
      (node (ref "JP1") (pin "MT1") (pinfunction "GND_MT1") (pintype "bidirectional"))
      (node (ref "JP1") (pin "MT2") (pinfunction "GND_MT2") (pintype "bidirectional"))
      (node (ref "JP2") (pin "1") (pinfunction "1_1") (pintype "passive"))
      (node (ref "Q1") (pin "2") (pinfunction "E_2") (pintype "passive"))
      (node (ref "Q2") (pin "2") (pinfunction "E_2") (pintype "passive"))
      (node (ref "Q3") (pin "2") (pinfunction "E_2") (pintype "passive"))
      (node (ref "R23") (pin "1") (pinfunction "1_1") (pintype "passive"))
      (node (ref "RA6") (pin "5") (pinfunction "2_5") (pintype "passive"))
      (node (ref "RA6") (pin "6") (pinfunction "2_6") (pintype "passive"))
      (node (ref "RA6") (pin "7") (pinfunction "2_7") (pintype "passive"))
      (node (ref "RA6") (pin "8") (pinfunction "2_8") (pintype "passive"))
      (node (ref "RA7") (pin "1") (pinfunction "1_1") (pintype "passive"))
      (node (ref "RA7") (pin "2") (pinfunction "1_2") (pintype "passive"))
      (node (ref "RA7") (pin "3") (pinfunction "1_3") (pintype "passive"))
      (node (ref "RA7") (pin "4") (pinfunction "1_4") (pintype "passive"))
      (node (ref "RA9") (pin "1") (pinfunction "1_1") (pintype "passive"))
      (node (ref "RA9") (pin "2") (pinfunction "1_2") (pintype "passive"))
      (node (ref "RA9") (pin "3") (pinfunction "1_3") (pintype "passive"))
      (node (ref "SW1") (pin "P2") (pinfunction "P2_P2") (pintype "bidirectional"))
      (node (ref "SW2") (pin "P2") (pinfunction "P2_P2") (pintype "bidirectional"))
      (node (ref "SW3") (pin "P2") (pinfunction "P2_P2") (pintype "bidirectional"))
      (node (ref "SW4") (pin "P2") (pinfunction "P2_P2") (pintype "bidirectional"))
      (node (ref "SW5") (pin "P2") (pinfunction "P2_P2") (pintype "bidirectional"))
      (node (ref "SW6") (pin "P2") (pinfunction "P2_P2") (pintype "bidirectional"))
      (node (ref "SW7") (pin "P2") (pinfunction "P2_P2") (pintype "bidirectional"))
      (node (ref "SW8") (pin "P2") (pinfunction "P2_P2") (pintype "bidirectional"))
      (node (ref "U$2") (pin "13") (pinfunction "GND_13") (pintype "bidirectional"))
      (node (ref "U$2") (pin "5") (pinfunction "GND_5") (pintype "bidirectional"))
      (node (ref "U$2") (pin "6") (pinfunction "~{CTS}_6") (pintype "bidirectional"))
      (node (ref "U$3") (pin "112") (pinfunction "GND_112") (pintype "bidirectional"))
      (node (ref "U$3") (pin "130") (pinfunction "GND_130") (pintype "bidirectional"))
      (node (ref "U$3") (pin "407") (pinfunction "GND_407") (pintype "bidirectional"))
      (node (ref "U$3") (pin "408") (pinfunction "GND_408") (pintype "bidirectional"))
      (node (ref "U$3") (pin "409") (pinfunction "GND_409") (pintype "bidirectional"))
      (node (ref "U$3") (pin "410") (pinfunction "GND_410") (pintype "bidirectional"))
      (node (ref "U$3") (pin "417") (pinfunction "GND_417") (pintype "bidirectional"))
      (node (ref "U$3") (pin "418") (pinfunction "GND_418") (pintype "bidirectional"))
      (node (ref "U$3") (pin "425") (pinfunction "GND_425") (pintype "bidirectional"))
      (node (ref "U$3") (pin "426") (pinfunction "GND_426") (pintype "bidirectional"))
      (node (ref "U$3") (pin "433") (pinfunction "GND_433") (pintype "bidirectional"))
      (node (ref "U$3") (pin "434") (pinfunction "GND_434") (pintype "bidirectional"))
      (node (ref "X2") (pin "10") (pinfunction "10_10") (pintype "passive"))
      (node (ref "X2") (pin "5") (pinfunction "5_5") (pintype "passive"))
      (node (ref "X2") (pin "6") (pinfunction "6_6") (pintype "passive"))
      (node (ref "X2") (pin "7") (pinfunction "7_7") (pintype "passive"))
      (node (ref "X2") (pin "8") (pinfunction "8_8") (pintype "passive"))
    )
    (net (code "70") (name "Net-(C5-Pad1)") (class "Default")
      (node (ref "C5") (pin "1") (pinfunction "1_1") (pintype "passive"))
      (node (ref "JP1") (pin "D+") (pinfunction "D+_D+") (pintype "bidirectional"))
      (node (ref "R1") (pin "1") (pinfunction "1_1") (pintype "passive"))
    )
    (net (code "71") (name "Net-(C6-Pad1)") (class "Default")
      (node (ref "C6") (pin "1") (pinfunction "1_1") (pintype "passive"))
      (node (ref "JP1") (pin "D-") (pinfunction "D-_D-") (pintype "bidirectional"))
      (node (ref "R2") (pin "1") (pinfunction "1_1") (pintype "passive"))
    )
    (net (code "72") (name "Net-(IC1A-A)") (class "Default")
      (node (ref "IC1") (pin "11") (pinfunction "A_11") (pintype "input"))
      (node (ref "RA7") (pin "6") (pinfunction "2_6") (pintype "passive"))
      (node (ref "S2") (pin "1") (pinfunction "1_1") (pintype "passive"))
    )
    (net (code "73") (name "Net-(IC1A-B)") (class "Default")
      (node (ref "IC1") (pin "12") (pinfunction "B_12") (pintype "input"))
      (node (ref "RA7") (pin "7") (pinfunction "2_7") (pintype "passive"))
      (node (ref "S3") (pin "1") (pinfunction "1_1") (pintype "passive"))
    )
    (net (code "74") (name "Net-(IC1A-C)") (class "Default")
      (node (ref "IC1") (pin "13") (pinfunction "C_13") (pintype "input"))
      (node (ref "RA7") (pin "8") (pinfunction "2_8") (pintype "passive"))
      (node (ref "S4") (pin "1") (pinfunction "1_1") (pintype "passive"))
    )
    (net (code "75") (name "Net-(IC1A-D)") (class "Default")
      (node (ref "IC1") (pin "14") (pinfunction "D_14") (pintype "input"))
      (node (ref "R23") (pin "2") (pinfunction "2_2") (pintype "passive"))
      (node (ref "S5") (pin "1") (pinfunction "1_1") (pintype "passive"))
    )
    (net (code "76") (name "Net-(IC1A-E)") (class "Default")
      (node (ref "IC1") (pin "3") (pinfunction "E_3") (pintype "input"))
      (node (ref "RA6") (pin "4") (pinfunction "1_4") (pintype "passive"))
      (node (ref "S6") (pin "1") (pinfunction "1_1") (pintype "passive"))
    )
    (net (code "77") (name "Net-(IC1A-F)") (class "Default")
      (node (ref "IC1") (pin "4") (pinfunction "F_4") (pintype "input"))
      (node (ref "RA6") (pin "3") (pinfunction "1_3") (pintype "passive"))
      (node (ref "S7") (pin "1") (pinfunction "1_1") (pintype "passive"))
    )
    (net (code "78") (name "Net-(IC1A-G)") (class "Default")
      (node (ref "IC1") (pin "5") (pinfunction "G_5") (pintype "input"))
      (node (ref "RA6") (pin "2") (pinfunction "1_2") (pintype "passive"))
      (node (ref "S8") (pin "1") (pinfunction "1_1") (pintype "passive"))
    )
    (net (code "79") (name "Net-(IC1A-H)") (class "Default")
      (node (ref "IC1") (pin "6") (pinfunction "H_6") (pintype "input"))
      (node (ref "RA6") (pin "1") (pinfunction "1_1") (pintype "passive"))
      (node (ref "S9") (pin "1") (pinfunction "1_1") (pintype "passive"))
    )
    (net (code "80") (name "Net-(IC1A-SER)") (class "Default")
      (node (ref "IC1") (pin "10") (pinfunction "SER_10") (pintype "input"))
      (node (ref "RA7") (pin "5") (pinfunction "2_5") (pintype "passive"))
      (node (ref "S1") (pin "1") (pinfunction "1_1") (pintype "passive"))
    )
    (net (code "81") (name "Net-(IC2A-A)") (class "Default")
      (node (ref "IC2") (pin "11") (pinfunction "A_11") (pintype "input"))
      (node (ref "SW1") (pin "C") (pinfunction "C_C") (pintype "bidirectional"))
    )
    (net (code "82") (name "Net-(IC2A-B)") (class "Default")
      (node (ref "IC2") (pin "12") (pinfunction "B_12") (pintype "input"))
      (node (ref "SW2") (pin "C") (pinfunction "C_C") (pintype "bidirectional"))
    )
    (net (code "83") (name "Net-(IC2A-C)") (class "Default")
      (node (ref "IC2") (pin "13") (pinfunction "C_13") (pintype "input"))
      (node (ref "SW3") (pin "C") (pinfunction "C_C") (pintype "bidirectional"))
    )
    (net (code "84") (name "Net-(IC2A-D)") (class "Default")
      (node (ref "IC2") (pin "14") (pinfunction "D_14") (pintype "input"))
      (node (ref "SW4") (pin "C") (pinfunction "C_C") (pintype "bidirectional"))
    )
    (net (code "85") (name "Net-(IC2A-E)") (class "Default")
      (node (ref "IC2") (pin "3") (pinfunction "E_3") (pintype "input"))
      (node (ref "SW5") (pin "C") (pinfunction "C_C") (pintype "bidirectional"))
    )
    (net (code "86") (name "Net-(IC2A-F)") (class "Default")
      (node (ref "IC2") (pin "4") (pinfunction "F_4") (pintype "input"))
      (node (ref "SW6") (pin "C") (pinfunction "C_C") (pintype "bidirectional"))
    )
    (net (code "87") (name "Net-(IC2A-G)") (class "Default")
      (node (ref "IC2") (pin "5") (pinfunction "G_5") (pintype "input"))
      (node (ref "SW7") (pin "C") (pinfunction "C_C") (pintype "bidirectional"))
    )
    (net (code "88") (name "Net-(IC2A-H)") (class "Default")
      (node (ref "IC2") (pin "6") (pinfunction "H_6") (pintype "input"))
      (node (ref "SW8") (pin "C") (pinfunction "C_C") (pintype "bidirectional"))
    )
    (net (code "89") (name "Net-(L9-11)") (class "Default")
      (node (ref "L9") (pin "P$11") (pinfunction "11_P$11") (pintype "bidirectional"))
      (node (ref "Q5") (pin "3") (pinfunction "C_3") (pintype "passive"))
    )
    (net (code "90") (name "Net-(L9-16)") (class "Default")
      (node (ref "L9") (pin "P$16") (pinfunction "16_P$16") (pintype "bidirectional"))
      (node (ref "Q4") (pin "3") (pinfunction "C_3") (pintype "passive"))
    )
    (net (code "91") (name "Net-(L10-1)") (class "Default")
      (node (ref "L10") (pin "P$1") (pinfunction "1_P$1") (pintype "bidirectional"))
      (node (ref "L11") (pin "P$1") (pinfunction "1_P$1") (pintype "bidirectional"))
      (node (ref "L12") (pin "P$1") (pinfunction "1_P$1") (pintype "bidirectional"))
      (node (ref "L9") (pin "P$1") (pinfunction "1_P$1") (pintype "bidirectional"))
      (node (ref "RA10") (pin "8") (pinfunction "2_8") (pintype "passive"))
    )
    (net (code "92") (name "Net-(L10-2)") (class "Default")
      (node (ref "L10") (pin "P$2") (pinfunction "2_P$2") (pintype "bidirectional"))
      (node (ref "L11") (pin "P$2") (pinfunction "2_P$2") (pintype "bidirectional"))
      (node (ref "L12") (pin "P$2") (pinfunction "2_P$2") (pintype "bidirectional"))
      (node (ref "L9") (pin "P$2") (pinfunction "2_P$2") (pintype "bidirectional"))
      (node (ref "RA10") (pin "7") (pinfunction "2_7") (pintype "passive"))
    )
    (net (code "93") (name "Net-(L10-4)") (class "Default")
      (node (ref "L10") (pin "P$4") (pinfunction "4_P$4") (pintype "bidirectional"))
      (node (ref "L11") (pin "P$4") (pinfunction "4_P$4") (pintype "bidirectional"))
      (node (ref "L12") (pin "P$4") (pinfunction "4_P$4") (pintype "bidirectional"))
      (node (ref "L9") (pin "P$4") (pinfunction "4_P$4") (pintype "bidirectional"))
      (node (ref "RA10") (pin "6") (pinfunction "2_6") (pintype "passive"))
    )
    (net (code "94") (name "Net-(L10-5)") (class "Default")
      (node (ref "L10") (pin "P$5") (pinfunction "5_P$5") (pintype "bidirectional"))
      (node (ref "L11") (pin "P$5") (pinfunction "5_P$5") (pintype "bidirectional"))
      (node (ref "L12") (pin "P$5") (pinfunction "5_P$5") (pintype "bidirectional"))
      (node (ref "L9") (pin "P$5") (pinfunction "5_P$5") (pintype "bidirectional"))
      (node (ref "RA10") (pin "5") (pinfunction "2_5") (pintype "passive"))
    )
    (net (code "95") (name "Net-(L10-6)") (class "Default")
      (node (ref "L10") (pin "P$6") (pinfunction "6_P$6") (pintype "bidirectional"))
      (node (ref "L11") (pin "P$6") (pinfunction "6_P$6") (pintype "bidirectional"))
      (node (ref "L12") (pin "P$6") (pinfunction "6_P$6") (pintype "bidirectional"))
      (node (ref "L9") (pin "P$6") (pinfunction "6_P$6") (pintype "bidirectional"))
      (node (ref "RA11") (pin "8") (pinfunction "2_8") (pintype "passive"))
    )
    (net (code "96") (name "Net-(L10-7)") (class "Default")
      (node (ref "L10") (pin "P$7") (pinfunction "7_P$7") (pintype "bidirectional"))
      (node (ref "L11") (pin "P$7") (pinfunction "7_P$7") (pintype "bidirectional"))
      (node (ref "L12") (pin "P$7") (pinfunction "7_P$7") (pintype "bidirectional"))
      (node (ref "L9") (pin "P$7") (pinfunction "7_P$7") (pintype "bidirectional"))
      (node (ref "RA11") (pin "7") (pinfunction "2_7") (pintype "passive"))
    )
    (net (code "97") (name "Net-(L10-8)") (class "Default")
      (node (ref "L10") (pin "P$8") (pinfunction "8_P$8") (pintype "bidirectional"))
      (node (ref "L11") (pin "P$8") (pinfunction "8_P$8") (pintype "bidirectional"))
      (node (ref "L12") (pin "P$8") (pinfunction "8_P$8") (pintype "bidirectional"))
      (node (ref "L9") (pin "P$8") (pinfunction "8_P$8") (pintype "bidirectional"))
      (node (ref "RA11") (pin "6") (pinfunction "2_6") (pintype "passive"))
    )
    (net (code "98") (name "Net-(L10-9)") (class "Default")
      (node (ref "L10") (pin "P$9") (pinfunction "9_P$9") (pintype "bidirectional"))
      (node (ref "L11") (pin "P$9") (pinfunction "9_P$9") (pintype "bidirectional"))
      (node (ref "L12") (pin "P$9") (pinfunction "9_P$9") (pintype "bidirectional"))
      (node (ref "L9") (pin "P$9") (pinfunction "9_P$9") (pintype "bidirectional"))
      (node (ref "RA11") (pin "5") (pinfunction "2_5") (pintype "passive"))
    )
    (net (code "99") (name "Net-(L10-10)") (class "Default")
      (node (ref "L10") (pin "P$10") (pinfunction "10_P$10") (pintype "bidirectional"))
      (node (ref "L11") (pin "P$10") (pinfunction "10_P$10") (pintype "bidirectional"))
      (node (ref "L12") (pin "P$10") (pinfunction "10_P$10") (pintype "bidirectional"))
      (node (ref "L9") (pin "P$10") (pinfunction "10_P$10") (pintype "bidirectional"))
      (node (ref "RA12") (pin "8") (pinfunction "2_8") (pintype "passive"))
    )
    (net (code "100") (name "Net-(L10-11)") (class "Default")
      (node (ref "L10") (pin "P$11") (pinfunction "11_P$11") (pintype "bidirectional"))
      (node (ref "Q7") (pin "3") (pinfunction "C_3") (pintype "passive"))
    )
    (net (code "101") (name "Net-(L10-12)") (class "Default")
      (node (ref "L10") (pin "P$12") (pinfunction "12_P$12") (pintype "bidirectional"))
      (node (ref "L11") (pin "P$12") (pinfunction "12_P$12") (pintype "bidirectional"))
      (node (ref "L12") (pin "P$12") (pinfunction "12_P$12") (pintype "bidirectional"))
      (node (ref "L9") (pin "P$12") (pinfunction "12_P$12") (pintype "bidirectional"))
      (node (ref "RA12") (pin "7") (pinfunction "2_7") (pintype "passive"))
    )
    (net (code "102") (name "Net-(L10-13)") (class "Default")
      (node (ref "L10") (pin "P$13") (pinfunction "13_P$13") (pintype "bidirectional"))
      (node (ref "L11") (pin "P$13") (pinfunction "13_P$13") (pintype "bidirectional"))
      (node (ref "L12") (pin "P$13") (pinfunction "13_P$13") (pintype "bidirectional"))
      (node (ref "L9") (pin "P$13") (pinfunction "13_P$13") (pintype "bidirectional"))
      (node (ref "RA12") (pin "6") (pinfunction "2_6") (pintype "passive"))
    )
    (net (code "103") (name "Net-(L10-14)") (class "Default")
      (node (ref "L10") (pin "P$14") (pinfunction "14_P$14") (pintype "bidirectional"))
      (node (ref "L11") (pin "P$14") (pinfunction "14_P$14") (pintype "bidirectional"))
      (node (ref "L12") (pin "P$14") (pinfunction "14_P$14") (pintype "bidirectional"))
      (node (ref "L9") (pin "P$14") (pinfunction "14_P$14") (pintype "bidirectional"))
      (node (ref "RA12") (pin "5") (pinfunction "2_5") (pintype "passive"))
    )
    (net (code "104") (name "Net-(L10-15)") (class "Default")
      (node (ref "L10") (pin "P$15") (pinfunction "15_P$15") (pintype "bidirectional"))
      (node (ref "L11") (pin "P$15") (pinfunction "15_P$15") (pintype "bidirectional"))
      (node (ref "L12") (pin "P$15") (pinfunction "15_P$15") (pintype "bidirectional"))
      (node (ref "L9") (pin "P$15") (pinfunction "15_P$15") (pintype "bidirectional"))
      (node (ref "RA13") (pin "8") (pinfunction "2_8") (pintype "passive"))
    )
    (net (code "105") (name "Net-(L10-16)") (class "Default")
      (node (ref "L10") (pin "P$16") (pinfunction "16_P$16") (pintype "bidirectional"))
      (node (ref "Q6") (pin "3") (pinfunction "C_3") (pintype "passive"))
    )
    (net (code "106") (name "Net-(L10-17)") (class "Default")
      (node (ref "L10") (pin "P$17") (pinfunction "17_P$17") (pintype "bidirectional"))
      (node (ref "L11") (pin "P$17") (pinfunction "17_P$17") (pintype "bidirectional"))
      (node (ref "L12") (pin "P$17") (pinfunction "17_P$17") (pintype "bidirectional"))
      (node (ref "L9") (pin "P$17") (pinfunction "17_P$17") (pintype "bidirectional"))
      (node (ref "RA13") (pin "7") (pinfunction "2_7") (pintype "passive"))
    )
    (net (code "107") (name "Net-(L10-18)") (class "Default")
      (node (ref "L10") (pin "P$18") (pinfunction "18_P$18") (pintype "bidirectional"))
      (node (ref "L11") (pin "P$18") (pinfunction "18_P$18") (pintype "bidirectional"))
      (node (ref "L12") (pin "P$18") (pinfunction "18_P$18") (pintype "bidirectional"))
      (node (ref "L9") (pin "P$18") (pinfunction "18_P$18") (pintype "bidirectional"))
      (node (ref "RA13") (pin "6") (pinfunction "2_6") (pintype "passive"))
    )
    (net (code "108") (name "Net-(L11-11)") (class "Default")
      (node (ref "L11") (pin "P$11") (pinfunction "11_P$11") (pintype "bidirectional"))
      (node (ref "Q9") (pin "3") (pinfunction "C_3") (pintype "passive"))
    )
    (net (code "109") (name "Net-(L11-16)") (class "Default")
      (node (ref "L11") (pin "P$16") (pinfunction "16_P$16") (pintype "bidirectional"))
      (node (ref "Q8") (pin "3") (pinfunction "C_3") (pintype "passive"))
    )
    (net (code "110") (name "Net-(L12-11)") (class "Default")
      (node (ref "L12") (pin "P$11") (pinfunction "11_P$11") (pintype "bidirectional"))
      (node (ref "Q11") (pin "3") (pinfunction "C_3") (pintype "passive"))
    )
    (net (code "111") (name "Net-(L12-16)") (class "Default")
      (node (ref "L12") (pin "P$16") (pinfunction "16_P$16") (pintype "bidirectional"))
      (node (ref "Q10") (pin "3") (pinfunction "C_3") (pintype "passive"))
    )
    (net (code "112") (name "Net-(L13-B)") (class "Default")
      (node (ref "L13") (pin "1") (pinfunction "B_1") (pintype "passive"))
      (node (ref "R22") (pin "2") (pinfunction "2_2") (pintype "passive"))
    )
    (net (code "113") (name "Net-(L13-G)") (class "Default")
      (node (ref "L13") (pin "3") (pinfunction "G_3") (pintype "passive"))
      (node (ref "R21") (pin "2") (pinfunction "2_2") (pintype "passive"))
    )
    (net (code "114") (name "Net-(L13-R)") (class "Default")
      (node (ref "L13") (pin "2") (pinfunction "R_2") (pintype "passive"))
      (node (ref "R20") (pin "2") (pinfunction "2_2") (pintype "passive"))
    )
    (net (code "115") (name "Net-(L14-PadC)") (class "Default")
      (node (ref "L14") (pin "C") (pinfunction "C_C") (pintype "passive"))
      (node (ref "R24") (pin "2") (pinfunction "2_2") (pintype "passive"))
    )
    (net (code "116") (name "Net-(L15-PadC)") (class "Default")
      (node (ref "L15") (pin "C") (pinfunction "C_C") (pintype "passive"))
      (node (ref "R25") (pin "2") (pinfunction "2_2") (pintype "passive"))
    )
    (net (code "117") (name "Net-(Q1-B)") (class "Default")
      (node (ref "Q1") (pin "1") (pinfunction "B_1") (pintype "passive"))
      (node (ref "RA8") (pin "8") (pinfunction "2_8") (pintype "passive"))
    )
    (net (code "118") (name "Net-(Q1-C)") (class "Default")
      (node (ref "Q1") (pin "3") (pinfunction "C_3") (pintype "passive"))
      (node (ref "R20") (pin "1") (pinfunction "1_1") (pintype "passive"))
    )
    (net (code "119") (name "Net-(Q2-B)") (class "Default")
      (node (ref "Q2") (pin "1") (pinfunction "B_1") (pintype "passive"))
      (node (ref "RA8") (pin "7") (pinfunction "2_7") (pintype "passive"))
    )
    (net (code "120") (name "Net-(Q2-C)") (class "Default")
      (node (ref "Q2") (pin "3") (pinfunction "C_3") (pintype "passive"))
      (node (ref "R21") (pin "1") (pinfunction "1_1") (pintype "passive"))
    )
    (net (code "121") (name "Net-(Q3-B)") (class "Default")
      (node (ref "Q3") (pin "1") (pinfunction "B_1") (pintype "passive"))
      (node (ref "RA8") (pin "6") (pinfunction "2_6") (pintype "passive"))
    )
    (net (code "122") (name "Net-(Q3-C)") (class "Default")
      (node (ref "Q3") (pin "3") (pinfunction "C_3") (pintype "passive"))
      (node (ref "R22") (pin "1") (pinfunction "1_1") (pintype "passive"))
    )
    (net (code "123") (name "Net-(Q4-B)") (class "Default")
      (node (ref "Q4") (pin "1") (pinfunction "B_1") (pintype "passive"))
      (node (ref "RA14") (pin "8") (pinfunction "2_8") (pintype "passive"))
    )
    (net (code "124") (name "Net-(Q5-B)") (class "Default")
      (node (ref "Q5") (pin "1") (pinfunction "B_1") (pintype "passive"))
      (node (ref "RA14") (pin "7") (pinfunction "2_7") (pintype "passive"))
    )
    (net (code "125") (name "Net-(Q6-B)") (class "Default")
      (node (ref "Q6") (pin "1") (pinfunction "B_1") (pintype "passive"))
      (node (ref "RA14") (pin "6") (pinfunction "2_6") (pintype "passive"))
    )
    (net (code "126") (name "Net-(Q7-B)") (class "Default")
      (node (ref "Q7") (pin "1") (pinfunction "B_1") (pintype "passive"))
      (node (ref "RA14") (pin "5") (pinfunction "2_5") (pintype "passive"))
    )
    (net (code "127") (name "Net-(Q8-B)") (class "Default")
      (node (ref "Q8") (pin "1") (pinfunction "B_1") (pintype "passive"))
      (node (ref "RA15") (pin "8") (pinfunction "2_8") (pintype "passive"))
    )
    (net (code "128") (name "Net-(Q9-B)") (class "Default")
      (node (ref "Q9") (pin "1") (pinfunction "B_1") (pintype "passive"))
      (node (ref "RA15") (pin "7") (pinfunction "2_7") (pintype "passive"))
    )
    (net (code "129") (name "Net-(Q10-B)") (class "Default")
      (node (ref "Q10") (pin "1") (pinfunction "B_1") (pintype "passive"))
      (node (ref "RA15") (pin "6") (pinfunction "2_6") (pintype "passive"))
    )
    (net (code "130") (name "Net-(Q11-B)") (class "Default")
      (node (ref "Q11") (pin "1") (pinfunction "B_1") (pintype "passive"))
      (node (ref "RA15") (pin "5") (pinfunction "2_5") (pintype "passive"))
    )
    (net (code "131") (name "Net-(R3-Pad1)") (class "Default")
      (node (ref "R3") (pin "1") (pinfunction "1_1") (pintype "passive"))
      (node (ref "X2") (pin "14") (pinfunction "14_14") (pintype "passive"))
    )
    (net (code "132") (name "Net-(R4-Pad1)") (class "Default")
      (node (ref "R4") (pin "1") (pinfunction "1_1") (pintype "passive"))
      (node (ref "X2") (pin "13") (pinfunction "13_13") (pintype "passive"))
    )
    (net (code "133") (name "Net-(R10-Pad2)") (class "Default")
      (node (ref "R10") (pin "2") (pinfunction "2_2") (pintype "passive"))
      (node (ref "R13") (pin "2") (pinfunction "2_2") (pintype "passive"))
      (node (ref "R16") (pin "2") (pinfunction "2_2") (pintype "passive"))
      (node (ref "R19") (pin "2") (pinfunction "2_2") (pintype "passive"))
      (node (ref "R7") (pin "2") (pinfunction "2_2") (pintype "passive"))
      (node (ref "X2") (pin "1") (pinfunction "1_1") (pintype "passive"))
    )
    (net (code "134") (name "Net-(R11-Pad2)") (class "Default")
      (node (ref "R11") (pin "2") (pinfunction "2_2") (pintype "passive"))
      (node (ref "R14") (pin "2") (pinfunction "2_2") (pintype "passive"))
      (node (ref "R17") (pin "2") (pinfunction "2_2") (pintype "passive"))
      (node (ref "R5") (pin "2") (pinfunction "2_2") (pintype "passive"))
      (node (ref "R8") (pin "2") (pinfunction "2_2") (pintype "passive"))
      (node (ref "X2") (pin "3") (pinfunction "3_3") (pintype "passive"))
    )
    (net (code "135") (name "Net-(R12-Pad2)") (class "Default")
      (node (ref "R12") (pin "2") (pinfunction "2_2") (pintype "passive"))
      (node (ref "R15") (pin "2") (pinfunction "2_2") (pintype "passive"))
      (node (ref "R18") (pin "2") (pinfunction "2_2") (pintype "passive"))
      (node (ref "R6") (pin "2") (pinfunction "2_2") (pintype "passive"))
      (node (ref "R9") (pin "2") (pinfunction "2_2") (pintype "passive"))
      (node (ref "X2") (pin "2") (pinfunction "2_2") (pintype "passive"))
    )
    (net (code "136") (name "Net-(RA1A-2)") (class "Default")
      (node (ref "L1") (pin "A") (pinfunction "A_A") (pintype "passive"))
      (node (ref "RA1") (pin "8") (pinfunction "2_8") (pintype "passive"))
    )
    (net (code "137") (name "Net-(RA1B-2)") (class "Default")
      (node (ref "L2") (pin "A") (pinfunction "A_A") (pintype "passive"))
      (node (ref "RA1") (pin "7") (pinfunction "2_7") (pintype "passive"))
    )
    (net (code "138") (name "Net-(RA1C-2)") (class "Default")
      (node (ref "L3") (pin "A") (pinfunction "A_A") (pintype "passive"))
      (node (ref "RA1") (pin "6") (pinfunction "2_6") (pintype "passive"))
    )
    (net (code "139") (name "Net-(RA1D-2)") (class "Default")
      (node (ref "L4") (pin "A") (pinfunction "A_A") (pintype "passive"))
      (node (ref "RA1") (pin "5") (pinfunction "2_5") (pintype "passive"))
    )
    (net (code "140") (name "Net-(RA2A-2)") (class "Default")
      (node (ref "L5") (pin "A") (pinfunction "A_A") (pintype "passive"))
      (node (ref "RA2") (pin "8") (pinfunction "2_8") (pintype "passive"))
    )
    (net (code "141") (name "Net-(RA2B-2)") (class "Default")
      (node (ref "L6") (pin "A") (pinfunction "A_A") (pintype "passive"))
      (node (ref "RA2") (pin "7") (pinfunction "2_7") (pintype "passive"))
    )
    (net (code "142") (name "Net-(RA2C-2)") (class "Default")
      (node (ref "L7") (pin "A") (pinfunction "A_A") (pintype "passive"))
      (node (ref "RA2") (pin "6") (pinfunction "2_6") (pintype "passive"))
    )
    (net (code "143") (name "Net-(RA2D-2)") (class "Default")
      (node (ref "L8") (pin "A") (pinfunction "A_A") (pintype "passive"))
      (node (ref "RA2") (pin "5") (pinfunction "2_5") (pintype "passive"))
    )
    (net (code "144") (name "Net-(U$2-3V3OUT)") (class "Default")
      (node (ref "C1") (pin "1") (pinfunction "1_1") (pintype "passive"))
      (node (ref "L14") (pin "A") (pinfunction "A_A") (pintype "passive"))
      (node (ref "L15") (pin "A") (pinfunction "A_A") (pintype "passive"))
      (node (ref "U$2") (pin "10") (pinfunction "3V3OUT_10") (pintype "bidirectional"))
      (node (ref "U$2") (pin "3") (pinfunction "VCCIO_3") (pintype "bidirectional"))
    )
    (net (code "145") (name "Net-(U$2-5V)") (class "Default")
      (node (ref "C2") (pin "1") (pinfunction "1_1") (pintype "passive"))
      (node (ref "JP1") (pin "VBUS") (pinfunction "VBUS_VBUS") (pintype "bidirectional"))
      (node (ref "U$2") (pin "12") (pinfunction "5V_12") (pintype "bidirectional"))
    )
    (net (code "146") (name "Net-(U$2-D+)") (class "Default")
      (node (ref "R1") (pin "2") (pinfunction "2_2") (pintype "passive"))
      (node (ref "U$2") (pin "8") (pinfunction "D+_8") (pintype "bidirectional"))
    )
    (net (code "147") (name "Net-(U$2-D-)") (class "Default")
      (node (ref "R2") (pin "2") (pinfunction "2_2") (pintype "passive"))
      (node (ref "U$2") (pin "9") (pinfunction "D-_9") (pintype "bidirectional"))
    )
    (net (code "148") (name "unconnected-(IC1A-~{QH}-Pad7)") (class "Default")
      (node (ref "IC1") (pin "7") (pinfunction "~{QH}_7") (pintype "output"))
    )
    (net (code "149") (name "unconnected-(IC2A-~{QH}-Pad7)") (class "Default")
      (node (ref "IC2") (pin "7") (pinfunction "~{QH}_7") (pintype "output"))
    )
    (net (code "150") (name "unconnected-(RA8D-1-Pad4)") (class "Default")
      (node (ref "RA8") (pin "4") (pinfunction "1_4") (pintype "passive"))
    )
    (net (code "151") (name "unconnected-(RA8D-2-Pad5)") (class "Default")
      (node (ref "RA8") (pin "5") (pinfunction "2_5") (pintype "passive"))
    )
    (net (code "152") (name "unconnected-(RA9D-1-Pad4)") (class "Default")
      (node (ref "RA9") (pin "4") (pinfunction "1_4") (pintype "passive"))
    )
    (net (code "153") (name "unconnected-(RA9D-2-Pad5)") (class "Default")
      (node (ref "RA9") (pin "5") (pinfunction "2_5") (pintype "passive"))
    )
    (net (code "154") (name "unconnected-(RA13D-1-Pad4)") (class "Default")
      (node (ref "RA13") (pin "4") (pinfunction "1_4") (pintype "passive"))
    )
    (net (code "155") (name "unconnected-(RA13D-2-Pad5)") (class "Default")
      (node (ref "RA13") (pin "5") (pinfunction "2_5") (pintype "passive"))
    )
    (net (code "156") (name "unconnected-(S1-Pad2)") (class "Default")
      (node (ref "S1") (pin "2") (pinfunction "2_2") (pintype "passive"))
    )
    (net (code "157") (name "unconnected-(S1-Pad4)") (class "Default")
      (node (ref "S1") (pin "4") (pinfunction "4_4") (pintype "passive"))
    )
    (net (code "158") (name "unconnected-(S2-Pad2)") (class "Default")
      (node (ref "S2") (pin "2") (pinfunction "2_2") (pintype "passive"))
    )
    (net (code "159") (name "unconnected-(S2-Pad4)") (class "Default")
      (node (ref "S2") (pin "4") (pinfunction "4_4") (pintype "passive"))
    )
    (net (code "160") (name "unconnected-(S3-Pad2)") (class "Default")
      (node (ref "S3") (pin "2") (pinfunction "2_2") (pintype "passive"))
    )
    (net (code "161") (name "unconnected-(S3-Pad4)") (class "Default")
      (node (ref "S3") (pin "4") (pinfunction "4_4") (pintype "passive"))
    )
    (net (code "162") (name "unconnected-(S4-Pad2)") (class "Default")
      (node (ref "S4") (pin "2") (pinfunction "2_2") (pintype "passive"))
    )
    (net (code "163") (name "unconnected-(S4-Pad4)") (class "Default")
      (node (ref "S4") (pin "4") (pinfunction "4_4") (pintype "passive"))
    )
    (net (code "164") (name "unconnected-(S5-Pad2)") (class "Default")
      (node (ref "S5") (pin "2") (pinfunction "2_2") (pintype "passive"))
    )
    (net (code "165") (name "unconnected-(S5-Pad4)") (class "Default")
      (node (ref "S5") (pin "4") (pinfunction "4_4") (pintype "passive"))
    )
    (net (code "166") (name "unconnected-(S6-Pad2)") (class "Default")
      (node (ref "S6") (pin "2") (pinfunction "2_2") (pintype "passive"))
    )
    (net (code "167") (name "unconnected-(S6-Pad4)") (class "Default")
      (node (ref "S6") (pin "4") (pinfunction "4_4") (pintype "passive"))
    )
    (net (code "168") (name "unconnected-(S7-Pad2)") (class "Default")
      (node (ref "S7") (pin "2") (pinfunction "2_2") (pintype "passive"))
    )
    (net (code "169") (name "unconnected-(S7-Pad4)") (class "Default")
      (node (ref "S7") (pin "4") (pinfunction "4_4") (pintype "passive"))
    )
    (net (code "170") (name "unconnected-(S8-Pad2)") (class "Default")
      (node (ref "S8") (pin "2") (pinfunction "2_2") (pintype "passive"))
    )
    (net (code "171") (name "unconnected-(S8-Pad4)") (class "Default")
      (node (ref "S8") (pin "4") (pinfunction "4_4") (pintype "passive"))
    )
    (net (code "172") (name "unconnected-(S9-Pad2)") (class "Default")
      (node (ref "S9") (pin "2") (pinfunction "2_2") (pintype "passive"))
    )
    (net (code "173") (name "unconnected-(S9-Pad4)") (class "Default")
      (node (ref "S9") (pin "4") (pinfunction "4_4") (pintype "passive"))
    )
    (net (code "174") (name "unconnected-(U$2-CBUS0-Pad15)") (class "Default")
      (node (ref "U$2") (pin "15") (pinfunction "CBUS0_15") (pintype "bidirectional"))
    )
    (net (code "175") (name "unconnected-(U$2-CBUS3-Pad16)") (class "Default")
      (node (ref "U$2") (pin "16") (pinfunction "CBUS3_16") (pintype "bidirectional"))
    )
    (net (code "176") (name "unconnected-(U$2-~{RESET}-Pad11)") (class "Default")
      (node (ref "U$2") (pin "11") (pinfunction "~{RESET}_11") (pintype "bidirectional"))
    )
    (net (code "177") (name "unconnected-(U$3-DIFF_RX_1--Pad140)") (class "Default")
      (node (ref "U$3") (pin "140") (pinfunction "DIFF_RX_1-_140") (pintype "bidirectional"))
    )
    (net (code "178") (name "unconnected-(X2-Pad4)") (class "Default")
      (node (ref "X2") (pin "4") (pinfunction "4_4") (pintype "passive"))
    )
    (net (code "179") (name "unconnected-(X2-Pad9)") (class "Default")
      (node (ref "X2") (pin "9") (pinfunction "9_9") (pintype "passive"))
    )
    (net (code "180") (name "unconnected-(X2-Pad11)") (class "Default")
      (node (ref "X2") (pin "11") (pinfunction "11_11") (pintype "passive"))
    )
    (net (code "181") (name "unconnected-(X2-Pad12)") (class "Default")
      (node (ref "X2") (pin "12") (pinfunction "12_12") (pintype "passive"))
    )
    (net (code "182") (name "unconnected-(X2-Pad15)") (class "Default")
      (node (ref "X2") (pin "15") (pinfunction "15_15") (pintype "passive"))
    )
  )
)
